# FIT_TCM_LOGIC.net
KiCad netlist of a schematic drawn in Altium Designer
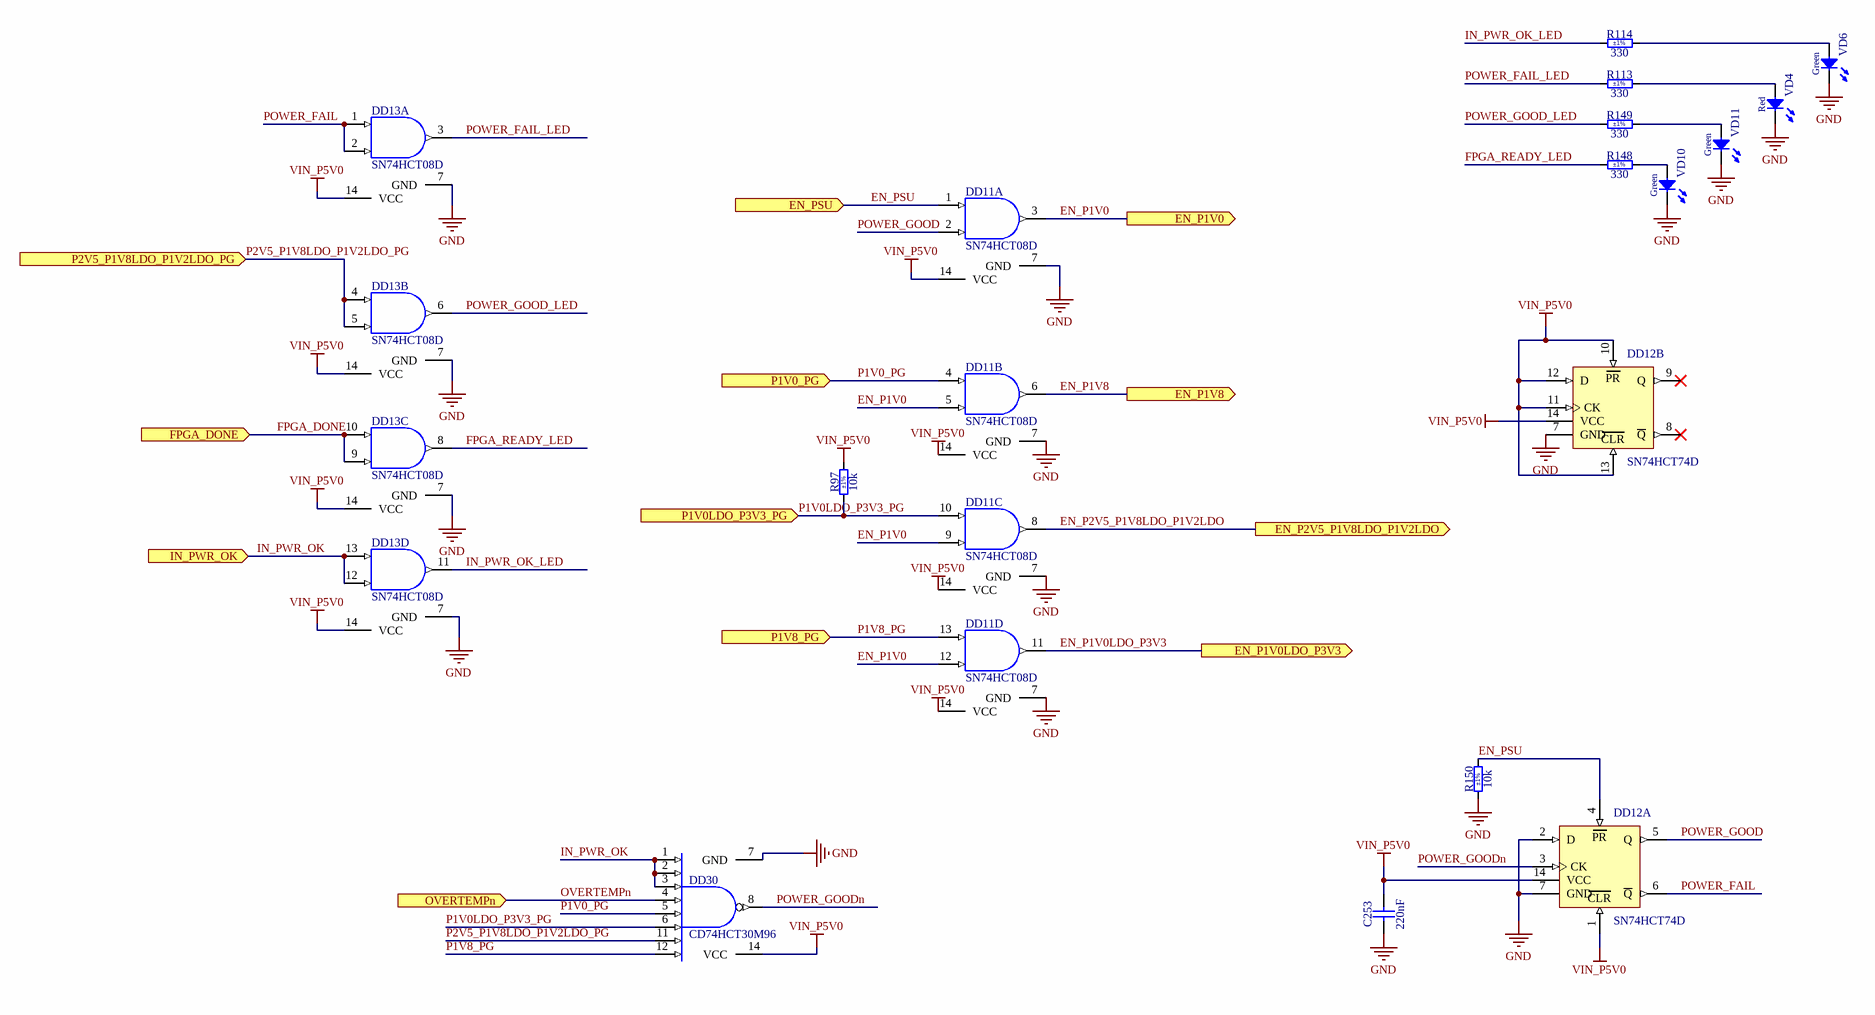
[diagram p0: FIT_TCM_LOGIC.SchDoc]

(export (version "E")
  (design (tool "Eeschema 10.0.6"))
  (components
    (comp (ref "C253")
      (value "220nF")
      (footprint "CAPC2012X135N")
      (description "Non-polarised capacitor")
      (fields
        (field (name "PART NUMBER") "CC0805_220NF_50V_10%_X7R")
        (field (name "VOLTAGE") "50V")
        (field (name "AUTHOR") "CERN DEM JLC")
      )
      (libsource (lib "Capacitors") (part "Capacitor - non polarized"))
    )
    (comp (ref "DD11")
      (value "SN74HCT08D")
      (footprint "SOIC127P600X175-14N")
      (description "Quad 2-Input AND Gate")
      (fields (field (name "MANUFACTURER") "TEXAS INSTRUMENTS") (field (name "AUTHOR") "CERN DEM HF"))
      (libsource (lib "ICs And Semiconductors") (part "7408"))
    )
    (comp (ref "DD12")
      (value "SN74HCT74D")
      (footprint "SOIC127P600X175-14N")
      (description "Dual D-Type Flip Flop with Preset and Clear")
      (fields (field (name "MANUFACTURER") "TEXAS INSTRUMENTS") (field (name "AUTHOR") "CERN DEM JLC"))
      (libsource (lib "ICs And Semiconductors") (part "7474"))
    )
    (comp (ref "DD13")
      (value "SN74HCT08D")
      (footprint "SOIC127P600X175-14N")
      (description "Quad 2-Input AND Gate")
      (fields (field (name "MANUFACTURER") "TEXAS INSTRUMENTS") (field (name "AUTHOR") "CERN DEM HF"))
      (libsource (lib "ICs And Semiconductors") (part "7408"))
    )
    (comp (ref "DD30")
      (value "CD74HCT30M96")
      (footprint "SOIC127P600X175-14N")
      (description "8-Input NAND Gate")
      (fields (field (name "MANUFACTURER") "TEXAS INSTRUMENTS") (field (name "AUTHOR") "CERN DEM HF"))
      (libsource (lib "ICs And Semiconductors") (part "7430"))
    )
    (comp (ref "R97")
      (value "10k")
      (footprint "RESC2012X60N")
      (description "Resistor - 1%")
      (fields
        (field (name "TOLERANCE") "±1%")
        (field (name "PART NUMBER") "R0805_10K_1%_0.125W_100PPM")
        (field (name "POWER") "0.125W")
        (field (name "AUTHOR") "CERN DEM JLC")
      )
      (libsource (lib "Resistors") (part "Resistor - 1%"))
    )
    (comp (ref "R113")
      (value "330")
      (footprint "RESC2012X60N")
      (description "Resistor - 1%")
      (fields
        (field (name "TOLERANCE") "±1%")
        (field (name "PART NUMBER") "R0805_330R_1%_0.125W_100PPM")
        (field (name "POWER") "0.125W")
        (field (name "AUTHOR") "CERN DEM JLC")
      )
      (libsource (lib "Resistors") (part "Resistor - 1%"))
    )
    (comp (ref "R114")
      (value "330")
      (footprint "RESC2012X60N")
      (description "Resistor - 1%")
      (fields
        (field (name "TOLERANCE") "±1%")
        (field (name "PART NUMBER") "R0805_330R_1%_0.125W_100PPM")
        (field (name "POWER") "0.125W")
        (field (name "AUTHOR") "CERN DEM JLC")
      )
      (libsource (lib "Resistors") (part "Resistor - 1%"))
    )
    (comp (ref "R148")
      (value "330")
      (footprint "RESC2012X60N")
      (description "Resistor - 1%")
      (fields
        (field (name "TOLERANCE") "±1%")
        (field (name "PART NUMBER") "R0805_330R_1%_0.125W_100PPM")
        (field (name "POWER") "0.125W")
        (field (name "AUTHOR") "CERN DEM JLC")
      )
      (libsource (lib "Resistors") (part "Resistor - 1%"))
    )
    (comp (ref "R149")
      (value "330")
      (footprint "RESC2012X60N")
      (description "Resistor - 1%")
      (fields
        (field (name "TOLERANCE") "±1%")
        (field (name "PART NUMBER") "R0805_330R_1%_0.125W_100PPM")
        (field (name "POWER") "0.125W")
        (field (name "AUTHOR") "CERN DEM JLC")
      )
      (libsource (lib "Resistors") (part "Resistor - 1%"))
    )
    (comp (ref "R150")
      (value "10k")
      (footprint "RESC2012X60N")
      (description "Resistor - 1%")
      (fields
        (field (name "TOLERANCE") "±1%")
        (field (name "PART NUMBER") "R0805_10K_1%_0.125W_100PPM")
        (field (name "POWER") "0.125W")
        (field (name "AUTHOR") "CERN DEM JLC")
      )
      (libsource (lib "Resistors") (part "Resistor - 1%"))
    )
    (comp (ref "VD4")
      (value "Red")
      (footprint "LED_KINGBRIGHT_KPT-2012SURCK")
      (description "LED Red 1C 2A")
      (fields
        (field (name "PART NUMBER") "LED_KINGBRIGHT_KPT-2012SURCK")
        (field (name "MANUFACTURER") "KINGBRIGHT")
        (field (name "AUTHOR") "CERN DEM BC")
      )
      (libsource (lib "ICs And Semiconductors") (part "LED Red 1C 2A"))
    )
    (comp (ref "VD6")
      (value "Green")
      (footprint "LED_KINGBRIGHT_KP-2012LSGC")
      (description "LED Green 1C 2A")
      (fields
        (field (name "PART NUMBER") "LED_KINGBRIGHT_KP-2012LSGC")
        (field (name "MANUFACTURER") "KINGBRIGHT")
        (field (name "AUTHOR") "CERN DEM BC")
      )
      (libsource (lib "ICs And Semiconductors") (part "LED Green 1C 2A"))
    )
    (comp (ref "VD10")
      (value "Green")
      (footprint "LED_KINGBRIGHT_KP-2012LSGC")
      (description "LED Green 1C 2A")
      (fields
        (field (name "PART NUMBER") "LED_KINGBRIGHT_KP-2012LSGC")
        (field (name "MANUFACTURER") "KINGBRIGHT")
        (field (name "AUTHOR") "CERN DEM BC")
      )
      (libsource (lib "ICs And Semiconductors") (part "LED Green 1C 2A"))
    )
    (comp (ref "VD11")
      (value "Green")
      (footprint "LED_KINGBRIGHT_KP-2012LSGC")
      (description "LED Green 1C 2A")
      (fields
        (field (name "PART NUMBER") "LED_KINGBRIGHT_KP-2012LSGC")
        (field (name "MANUFACTURER") "KINGBRIGHT")
        (field (name "AUTHOR") "CERN DEM BC")
      )
      (libsource (lib "ICs And Semiconductors") (part "LED Green 1C 2A"))
    )
  )
  (nets
    (net (code "1") (name "/EN_P1V0") (class "Default")
      (node (ref "DD11") (pin "12") (pinfunction "B_12") (pintype "input"))
      (node (ref "DD11") (pin "3") (pinfunction "Y_3") (pintype "output"))
      (node (ref "DD11") (pin "5") (pinfunction "B_5") (pintype "input"))
      (node (ref "DD11") (pin "9") (pinfunction "B_9") (pintype "input"))
    )
    (net (code "2") (name "/EN_P1V0LDO_P3V3") (class "Default")
      (node (ref "DD11") (pin "11") (pinfunction "Y_11") (pintype "output"))
    )
    (net (code "3") (name "/EN_P1V8") (class "Default")
      (node (ref "DD11") (pin "6") (pinfunction "Y_6") (pintype "output"))
    )
    (net (code "4") (name "/EN_P2V5_P1V8LDO_P1V2LDO") (class "Default")
      (node (ref "DD11") (pin "8") (pinfunction "Y_8") (pintype "output"))
    )
    (net (code "5") (name "/EN_PSU") (class "Default")
      (node (ref "DD11") (pin "1") (pinfunction "A_1") (pintype "input"))
      (node (ref "DD12") (pin "4") (pinfunction "~{PR}_4") (pintype "input"))
      (node (ref "R150") (pin "2") (pinfunction "2_2") (pintype "passive"))
    )
    (net (code "6") (name "/FPGA_DONE") (class "Default")
      (node (ref "DD13") (pin "10") (pinfunction "A_10") (pintype "input"))
      (node (ref "DD13") (pin "9") (pinfunction "B_9") (pintype "input"))
    )
    (net (code "7") (name "/FPGA_READY_LED") (class "Default")
      (node (ref "DD13") (pin "8") (pinfunction "Y_8") (pintype "output"))
      (node (ref "R148") (pin "1") (pinfunction "1_1") (pintype "passive"))
    )
    (net (code "8") (name "/IN_PWR_OK") (class "Default")
      (node (ref "DD13") (pin "12") (pinfunction "B_12") (pintype "input"))
      (node (ref "DD13") (pin "13") (pinfunction "A_13") (pintype "input"))
      (node (ref "DD30") (pin "1") (pinfunction "A_1") (pintype "input"))
      (node (ref "DD30") (pin "2") (pinfunction "B_2") (pintype "input"))
      (node (ref "DD30") (pin "3") (pinfunction "C_3") (pintype "input"))
    )
    (net (code "9") (name "/IN_PWR_OK_LED") (class "Default")
      (node (ref "DD13") (pin "11") (pinfunction "Y_11") (pintype "output"))
      (node (ref "R114") (pin "1") (pinfunction "1_1") (pintype "passive"))
    )
    (net (code "10") (name "/OVERTEMPn") (class "Default")
      (node (ref "DD30") (pin "4") (pinfunction "D_4") (pintype "input"))
    )
    (net (code "11") (name "/P1V0LDO_P3V3_PG") (class "Default")
      (node (ref "DD11") (pin "10") (pinfunction "A_10") (pintype "input"))
      (node (ref "DD30") (pin "6") (pinfunction "F_6") (pintype "input"))
      (node (ref "R97") (pin "1") (pinfunction "1_1") (pintype "passive"))
    )
    (net (code "12") (name "/P1V0_PG") (class "Default")
      (node (ref "DD11") (pin "4") (pinfunction "A_4") (pintype "input"))
      (node (ref "DD30") (pin "5") (pinfunction "E_5") (pintype "input"))
    )
    (net (code "13") (name "/P1V8_PG") (class "Default")
      (node (ref "DD11") (pin "13") (pinfunction "A_13") (pintype "input"))
      (node (ref "DD30") (pin "12") (pinfunction "H_12") (pintype "input"))
    )
    (net (code "14") (name "/P2V5_P1V8LDO_P1V2LDO_PG") (class "Default")
      (node (ref "DD13") (pin "4") (pinfunction "A_4") (pintype "input"))
      (node (ref "DD13") (pin "5") (pinfunction "B_5") (pintype "input"))
      (node (ref "DD30") (pin "11") (pinfunction "G_11") (pintype "input"))
    )
    (net (code "15") (name "/POWER_FAIL") (class "Default")
      (node (ref "DD12") (pin "6") (pinfunction "~{Q}_6") (pintype "output"))
      (node (ref "DD13") (pin "1") (pinfunction "A_1") (pintype "input"))
      (node (ref "DD13") (pin "2") (pinfunction "B_2") (pintype "input"))
    )
    (net (code "16") (name "/POWER_FAIL_LED") (class "Default")
      (node (ref "DD13") (pin "3") (pinfunction "Y_3") (pintype "output"))
      (node (ref "R113") (pin "1") (pinfunction "1_1") (pintype "passive"))
    )
    (net (code "17") (name "/POWER_GOOD") (class "Default")
      (node (ref "DD11") (pin "2") (pinfunction "B_2") (pintype "input"))
      (node (ref "DD12") (pin "5") (pinfunction "Q_5") (pintype "output"))
    )
    (net (code "18") (name "/POWER_GOOD_LED") (class "Default")
      (node (ref "DD13") (pin "6") (pinfunction "Y_6") (pintype "output"))
      (node (ref "R149") (pin "1") (pinfunction "1_1") (pintype "passive"))
    )
    (net (code "19") (name "/POWER_GOODn") (class "Default")
      (node (ref "DD12") (pin "3") (pinfunction "CK_3") (pintype "input"))
      (node (ref "DD30") (pin "8") (pinfunction "Y_8") (pintype "output"))
    )
    (net (code "20") (name "GND") (class "Default")
      (node (ref "C253") (pin "1") (pinfunction "1_1") (pintype "passive"))
      (node (ref "DD11") (pin "7") (pinfunction "GND_7") (pintype "power_in"))
      (node (ref "DD12") (pin "2") (pinfunction "D_2") (pintype "input"))
      (node (ref "DD12") (pin "7") (pinfunction "GND_7") (pintype "power_in"))
      (node (ref "DD13") (pin "7") (pinfunction "GND_7") (pintype "power_in"))
      (node (ref "DD30") (pin "7") (pinfunction "GND_7") (pintype "power_in"))
      (node (ref "R150") (pin "1") (pinfunction "1_1") (pintype "passive"))
      (node (ref "VD10") (pin "1") (pinfunction "C_1") (pintype "passive"))
      (node (ref "VD11") (pin "1") (pinfunction "C_1") (pintype "passive"))
      (node (ref "VD4") (pin "1") (pinfunction "C_1") (pintype "passive"))
      (node (ref "VD6") (pin "1") (pinfunction "C_1") (pintype "passive"))
    )
    (net (code "21") (name "Net-(VD4-A)") (class "Default")
      (node (ref "R113") (pin "2") (pinfunction "2_2") (pintype "passive"))
      (node (ref "VD4") (pin "2") (pinfunction "A_2") (pintype "passive"))
    )
    (net (code "22") (name "Net-(VD6-A)") (class "Default")
      (node (ref "R114") (pin "2") (pinfunction "2_2") (pintype "passive"))
      (node (ref "VD6") (pin "2") (pinfunction "A_2") (pintype "passive"))
    )
    (net (code "23") (name "Net-(VD10-A)") (class "Default")
      (node (ref "R148") (pin "2") (pinfunction "2_2") (pintype "passive"))
      (node (ref "VD10") (pin "2") (pinfunction "A_2") (pintype "passive"))
    )
    (net (code "24") (name "Net-(VD11-A)") (class "Default")
      (node (ref "R149") (pin "2") (pinfunction "2_2") (pintype "passive"))
      (node (ref "VD11") (pin "2") (pinfunction "A_2") (pintype "passive"))
    )
    (net (code "25") (name "VIN_P5V0") (class "Default")
      (node (ref "C253") (pin "2") (pinfunction "2_2") (pintype "passive"))
      (node (ref "DD11") (pin "14") (pinfunction "VCC_14") (pintype "power_in"))
      (node (ref "DD12") (pin "1") (pinfunction "~{CLR}_1") (pintype "input"))
      (node (ref "DD12") (pin "10") (pinfunction "~{PR}_10") (pintype "input"))
      (node (ref "DD12") (pin "11") (pinfunction "CK_11") (pintype "input"))
      (node (ref "DD12") (pin "12") (pinfunction "D_12") (pintype "input"))
      (node (ref "DD12") (pin "13") (pinfunction "~{CLR}_13") (pintype "input"))
      (node (ref "DD12") (pin "14") (pinfunction "VCC_14") (pintype "power_in"))
      (node (ref "DD13") (pin "14") (pinfunction "VCC_14") (pintype "power_in"))
      (node (ref "DD30") (pin "14") (pinfunction "VCC_14") (pintype "power_in"))
      (node (ref "R97") (pin "2") (pinfunction "2_2") (pintype "passive"))
    )
    (net (code "26") (name "unconnected-(DD12B-Q-Pad9)") (class "Default")
      (node (ref "DD12") (pin "9") (pinfunction "Q_9") (pintype "output+no_connect"))
    )
    (net (code "27") (name "unconnected-(DD12B-~{Q}-Pad8)") (class "Default")
      (node (ref "DD12") (pin "8") (pinfunction "~{Q}_8") (pintype "output+no_connect"))
    )
  )
)
